# NBMC_SCHEMATIC_with_LBM313.net
KiCad netlist of a schematic drawn in EAGLE
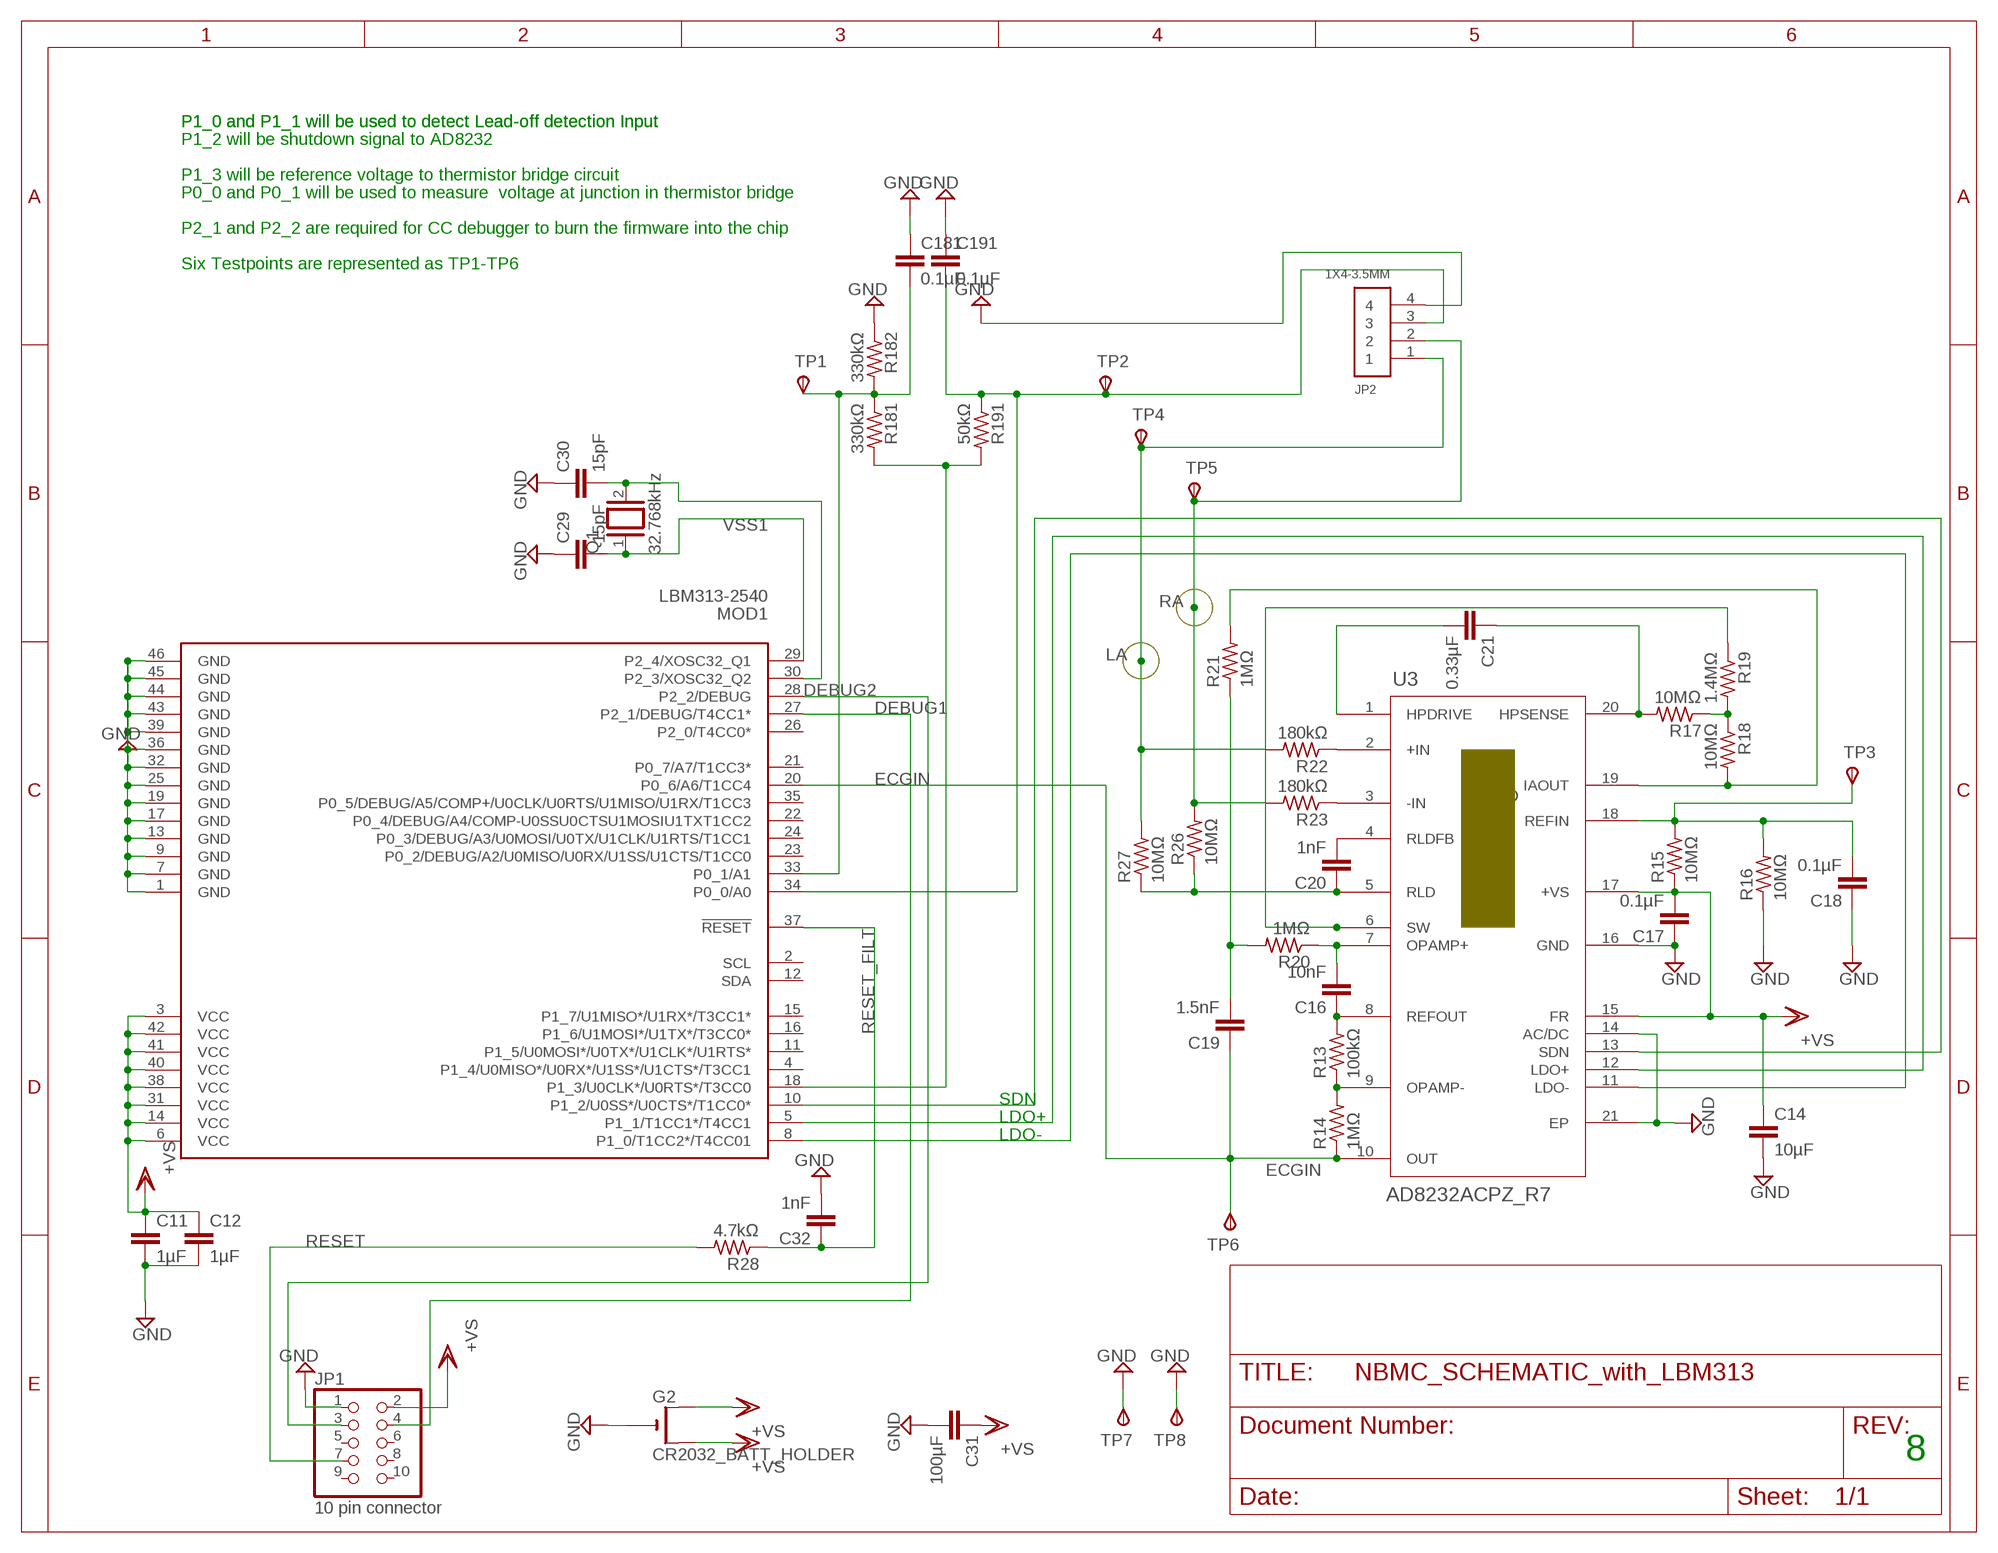
[diagram p0: schematic, sheet 1]

(export (version "E")
  (design (tool "Eeschema 10.0.6"))
  (components
    (comp (ref "C11")
      (value "1µF")
      (footprint "eagle-import:C0402")
      (libsource (lib "eagle-import") (part "C-EUC0402"))
    )
    (comp (ref "C12")
      (value "1µF")
      (footprint "eagle-import:C0402")
      (libsource (lib "eagle-import") (part "C-EUC0402"))
    )
    (comp (ref "C14")
      (value "10µF")
      (footprint "eagle-import:C0402")
      (libsource (lib "eagle-import") (part "C-EUC0402"))
    )
    (comp (ref "C16")
      (value "10nF")
      (footprint "eagle-import:C0402")
      (libsource (lib "eagle-import") (part "C-EUC0402"))
    )
    (comp (ref "C17")
      (value "0.1µF")
      (footprint "eagle-import:C0402")
      (libsource (lib "eagle-import") (part "C-EUC0402"))
    )
    (comp (ref "C18")
      (value "0.1µF")
      (footprint "eagle-import:C0402")
      (libsource (lib "eagle-import") (part "C-EUC0402"))
    )
    (comp (ref "C19")
      (value "1.5nF")
      (footprint "eagle-import:C0402")
      (libsource (lib "eagle-import") (part "C-EUC0402"))
    )
    (comp (ref "C20")
      (value "1nF")
      (footprint "eagle-import:C0402")
      (libsource (lib "eagle-import") (part "C-EUC0402"))
    )
    (comp (ref "C21")
      (value "0.33µF")
      (footprint "eagle-import:C0402")
      (libsource (lib "eagle-import") (part "C-EUC0402"))
    )
    (comp (ref "C29")
      (value "15pF")
      (footprint "eagle-import:C0402")
      (libsource (lib "eagle-import") (part "C-EUC0402"))
    )
    (comp (ref "C30")
      (value "15pF")
      (footprint "eagle-import:C0402")
      (libsource (lib "eagle-import") (part "C-EUC0402"))
    )
    (comp (ref "C31")
      (value "100µF")
      (footprint "eagle-import:C1210")
      (libsource (lib "eagle-import") (part "resistor_C-EUC1210"))
    )
    (comp (ref "C32")
      (value "1nF")
      (footprint "eagle-import:C0402")
      (libsource (lib "eagle-import") (part "C-EUC0402"))
    )
    (comp (ref "C181")
      (value "0.1µF")
      (footprint "eagle-import:C0402")
      (libsource (lib "eagle-import") (part "C-EUC0402"))
    )
    (comp (ref "C191")
      (value "0.1µF")
      (footprint "eagle-import:C0402")
      (libsource (lib "eagle-import") (part "C-EUC0402"))
    )
    (comp (ref "G2")
      (value "CR2032_BATT_HOLDER")
      (footprint "eagle-import:CR2032-SMD")
      (libsource (lib "eagle-import") (part "CR2032SMT"))
    )
    (comp (ref "JP1")
      (value "10 pin connector")
      (footprint "eagle-import:2X05")
      (libsource (lib "eagle-import") (part "PINHD-2X5"))
    )
    (comp (ref "JP2")
      (value "1X4-3.5MM")
      (footprint "eagle-import:1X04-3.5MM")
      (libsource (lib "eagle-import") (part "1X4-3.5MM"))
    )
    (comp (ref "MOD1")
      (value "LBM313-2540")
      (footprint "eagle-import:LBM313-2540")
      (libsource (lib "eagle-import") (part "LBM313-2540"))
    )
    (comp (ref "Q1")
      (value "32.768kHz")
      (footprint "eagle-import:Q")
      (libsource (lib "eagle-import") (part "XTAL"))
    )
    (comp (ref "R13")
      (value "100kΩ")
      (footprint "eagle-import:R0402")
      (libsource (lib "eagle-import") (part "R-US_R0402"))
    )
    (comp (ref "R14")
      (value "1MΩ")
      (footprint "eagle-import:R0402")
      (libsource (lib "eagle-import") (part "R-US_R0402"))
    )
    (comp (ref "R15")
      (value "10MΩ")
      (footprint "eagle-import:R0402")
      (libsource (lib "eagle-import") (part "R-US_R0402"))
    )
    (comp (ref "R16")
      (value "10MΩ")
      (footprint "eagle-import:R0402")
      (libsource (lib "eagle-import") (part "R-US_R0402"))
    )
    (comp (ref "R17")
      (value "10MΩ")
      (footprint "eagle-import:R0402")
      (libsource (lib "eagle-import") (part "R-US_R0402"))
    )
    (comp (ref "R18")
      (value "10MΩ")
      (footprint "eagle-import:R0402")
      (libsource (lib "eagle-import") (part "R-US_R0402"))
    )
    (comp (ref "R19")
      (value "1.4MΩ")
      (footprint "eagle-import:R0402")
      (libsource (lib "eagle-import") (part "R-US_R0402"))
    )
    (comp (ref "R20")
      (value "1MΩ")
      (footprint "eagle-import:R0402")
      (libsource (lib "eagle-import") (part "R-US_R0402"))
    )
    (comp (ref "R21")
      (value "1MΩ")
      (footprint "eagle-import:R0402")
      (libsource (lib "eagle-import") (part "R-US_R0402"))
    )
    (comp (ref "R22")
      (value "180kΩ")
      (footprint "eagle-import:R0402")
      (libsource (lib "eagle-import") (part "R-US_R0402"))
    )
    (comp (ref "R23")
      (value "180kΩ")
      (footprint "eagle-import:R0402")
      (libsource (lib "eagle-import") (part "R-US_R0402"))
    )
    (comp (ref "R26")
      (value "10MΩ")
      (footprint "eagle-import:R0402")
      (libsource (lib "eagle-import") (part "R-US_R0402"))
    )
    (comp (ref "R27")
      (value "10MΩ")
      (footprint "eagle-import:R0402")
      (libsource (lib "eagle-import") (part "R-US_R0402"))
    )
    (comp (ref "R28")
      (value "4.7kΩ")
      (footprint "eagle-import:R0402")
      (libsource (lib "eagle-import") (part "R-US_R0402"))
    )
    (comp (ref "R181")
      (value "330kΩ")
      (footprint "eagle-import:R0402")
      (libsource (lib "eagle-import") (part "R-US_R0402"))
    )
    (comp (ref "R182")
      (value "330kΩ")
      (footprint "eagle-import:R0402")
      (libsource (lib "eagle-import") (part "R-US_R0402"))
    )
    (comp (ref "R191")
      (value "50kΩ")
      (footprint "eagle-import:R0402")
      (libsource (lib "eagle-import") (part "R-US_R0402"))
    )
    (comp (ref "TP1")
      (value "TPSTP09R")
      (footprint "eagle-import:TP09R")
      (libsource (lib "eagle-import") (part "TPSTP09R"))
    )
    (comp (ref "TP2")
      (value "TPSTP09R")
      (footprint "eagle-import:TP09R")
      (libsource (lib "eagle-import") (part "TPSTP09R"))
    )
    (comp (ref "TP3")
      (value "TPSTP09R")
      (footprint "eagle-import:TP09R")
      (libsource (lib "eagle-import") (part "TPSTP09R"))
    )
    (comp (ref "TP4")
      (value "TPSTP09R")
      (footprint "eagle-import:TP09R")
      (libsource (lib "eagle-import") (part "TPSTP09R"))
    )
    (comp (ref "TP5")
      (value "TPSTP09R")
      (footprint "eagle-import:TP09R")
      (libsource (lib "eagle-import") (part "TPSTP09R"))
    )
    (comp (ref "TP6")
      (value "TPSTP09R")
      (footprint "eagle-import:TP09R")
      (libsource (lib "eagle-import") (part "TPSTP09R"))
    )
    (comp (ref "TP7")
      (value "TPSTP09R")
      (footprint "eagle-import:TP09R")
      (libsource (lib "eagle-import") (part "TPSTP09R"))
    )
    (comp (ref "TP8")
      (value "TPSTP09R")
      (footprint "eagle-import:TP09R")
      (libsource (lib "eagle-import") (part "TPSTP09R"))
    )
    (comp (ref "U3")
      (value "AD8232ACPZ_R7")
      (footprint "eagle-import:CP_20_10")
      (libsource (lib "eagle-import") (part "AD8232ACPZ_R7"))
    )
  )
  (nets
    (net (code "1") (name "+VS") (class "Default")
      (node (ref "C11") (pin "1") (pinfunction "1_1") (pintype "passive"))
      (node (ref "C12") (pin "1") (pinfunction "1_1") (pintype "passive"))
      (node (ref "C14") (pin "1") (pinfunction "1_1") (pintype "passive"))
      (node (ref "C17") (pin "2") (pinfunction "2_2") (pintype "passive"))
      (node (ref "C31") (pin "1") (pinfunction "1_1") (pintype "passive"))
      (node (ref "G2") (pin "1") (pinfunction "VS1_1") (pintype "passive"))
      (node (ref "G2") (pin "3") (pinfunction "VS2_3") (pintype "passive"))
      (node (ref "JP1") (pin "2") (pinfunction "2_2") (pintype "passive"))
      (node (ref "MOD1") (pin "14") (pinfunction "VCC_14") (pintype "bidirectional"))
      (node (ref "MOD1") (pin "3") (pinfunction "VCC_3") (pintype "bidirectional"))
      (node (ref "MOD1") (pin "31") (pinfunction "VCC_31") (pintype "bidirectional"))
      (node (ref "MOD1") (pin "38") (pinfunction "VCC_38") (pintype "bidirectional"))
      (node (ref "MOD1") (pin "40") (pinfunction "VCC_40") (pintype "bidirectional"))
      (node (ref "MOD1") (pin "41") (pinfunction "VCC_41") (pintype "bidirectional"))
      (node (ref "MOD1") (pin "42") (pinfunction "VCC_42") (pintype "bidirectional"))
      (node (ref "MOD1") (pin "6") (pinfunction "VCC_6") (pintype "bidirectional"))
      (node (ref "R15") (pin "1") (pinfunction "1_1") (pintype "passive"))
      (node (ref "U3") (pin "15") (pinfunction "FR_15") (pintype "passive"))
      (node (ref "U3") (pin "17") (pinfunction "+VS_17") (pintype "passive"))
    )
    (net (code "2") (name "/DEBUG1") (class "Default")
      (node (ref "JP1") (pin "4") (pinfunction "4_4") (pintype "passive"))
      (node (ref "MOD1") (pin "27") (pinfunction "P2_1/DEBUG/T4CC1*_27") (pintype "bidirectional"))
    )
    (net (code "3") (name "/DEBUG2") (class "Default")
      (node (ref "JP1") (pin "3") (pinfunction "3_3") (pintype "passive"))
      (node (ref "MOD1") (pin "28") (pinfunction "P2_2/DEBUG_28") (pintype "bidirectional"))
    )
    (net (code "4") (name "/ECGIN") (class "Default")
      (node (ref "C19") (pin "1") (pinfunction "1_1") (pintype "passive"))
      (node (ref "MOD1") (pin "20") (pinfunction "P0_6/A6/T1CC4_20") (pintype "bidirectional"))
      (node (ref "R14") (pin "1") (pinfunction "1_1") (pintype "passive"))
      (node (ref "TP6") (pin "TP") (pinfunction "PP_TP") (pintype "input"))
      (node (ref "U3") (pin "10") (pinfunction "OUT_10") (pintype "passive"))
    )
    (net (code "5") (name "/LA") (class "Default")
      (node (ref "JP2") (pin "1") (pinfunction "1_1") (pintype "bidirectional"))
      (node (ref "R22") (pin "2") (pinfunction "2_2") (pintype "passive"))
      (node (ref "R27") (pin "2") (pinfunction "2_2") (pintype "passive"))
      (node (ref "TP4") (pin "TP") (pinfunction "PP_TP") (pintype "input"))
    )
    (net (code "6") (name "/RA") (class "Default")
      (node (ref "JP2") (pin "2") (pinfunction "2_2") (pintype "bidirectional"))
      (node (ref "R23") (pin "2") (pinfunction "2_2") (pintype "passive"))
      (node (ref "R26") (pin "2") (pinfunction "2_2") (pintype "passive"))
      (node (ref "TP5") (pin "TP") (pinfunction "PP_TP") (pintype "input"))
    )
    (net (code "7") (name "/RESET") (class "Default")
      (node (ref "JP1") (pin "7") (pinfunction "7_7") (pintype "passive"))
      (node (ref "R28") (pin "2") (pinfunction "2_2") (pintype "passive"))
    )
    (net (code "8") (name "/RESET_FILT") (class "Default")
      (node (ref "C32") (pin "1") (pinfunction "1_1") (pintype "passive"))
      (node (ref "MOD1") (pin "37") (pinfunction "~{RESET}_37") (pintype "bidirectional"))
      (node (ref "R28") (pin "1") (pinfunction "1_1") (pintype "passive"))
    )
    (net (code "9") (name "/VSS1") (class "Default")
      (node (ref "C29") (pin "2") (pinfunction "2_2") (pintype "passive"))
      (node (ref "MOD1") (pin "29") (pinfunction "P2_4/XOSC32_Q1_29") (pintype "bidirectional"))
      (node (ref "Q1") (pin "1") (pinfunction "1_1") (pintype "passive"))
    )
    (net (code "10") (name "GND") (class "Default")
      (node (ref "C11") (pin "2") (pinfunction "2_2") (pintype "passive"))
      (node (ref "C12") (pin "2") (pinfunction "2_2") (pintype "passive"))
      (node (ref "C14") (pin "2") (pinfunction "2_2") (pintype "passive"))
      (node (ref "C17") (pin "1") (pinfunction "1_1") (pintype "passive"))
      (node (ref "C18") (pin "1") (pinfunction "1_1") (pintype "passive"))
      (node (ref "C181") (pin "1") (pinfunction "1_1") (pintype "passive"))
      (node (ref "C191") (pin "1") (pinfunction "1_1") (pintype "passive"))
      (node (ref "C29") (pin "1") (pinfunction "1_1") (pintype "passive"))
      (node (ref "C30") (pin "1") (pinfunction "1_1") (pintype "passive"))
      (node (ref "C31") (pin "2") (pinfunction "2_2") (pintype "passive"))
      (node (ref "C32") (pin "2") (pinfunction "2_2") (pintype "passive"))
      (node (ref "G2") (pin "2") (pinfunction "GND_2") (pintype "passive"))
      (node (ref "JP1") (pin "1") (pinfunction "1_1") (pintype "passive"))
      (node (ref "JP2") (pin "4") (pinfunction "4_4") (pintype "bidirectional"))
      (node (ref "MOD1") (pin "1") (pinfunction "GND_1") (pintype "bidirectional"))
      (node (ref "MOD1") (pin "13") (pinfunction "GND_13") (pintype "bidirectional"))
      (node (ref "MOD1") (pin "17") (pinfunction "GND_17") (pintype "bidirectional"))
      (node (ref "MOD1") (pin "19") (pinfunction "GND_19") (pintype "bidirectional"))
      (node (ref "MOD1") (pin "25") (pinfunction "GND_25") (pintype "bidirectional"))
      (node (ref "MOD1") (pin "32") (pinfunction "GND_32") (pintype "bidirectional"))
      (node (ref "MOD1") (pin "36") (pinfunction "GND_36") (pintype "bidirectional"))
      (node (ref "MOD1") (pin "39") (pinfunction "GND_39") (pintype "bidirectional"))
      (node (ref "MOD1") (pin "43") (pinfunction "GND_43") (pintype "bidirectional"))
      (node (ref "MOD1") (pin "44") (pinfunction "GND_44") (pintype "bidirectional"))
      (node (ref "MOD1") (pin "45") (pinfunction "GND_45") (pintype "bidirectional"))
      (node (ref "MOD1") (pin "46") (pinfunction "GND_46") (pintype "bidirectional"))
      (node (ref "MOD1") (pin "7") (pinfunction "GND_7") (pintype "bidirectional"))
      (node (ref "MOD1") (pin "9") (pinfunction "GND_9") (pintype "bidirectional"))
      (node (ref "R16") (pin "1") (pinfunction "1_1") (pintype "passive"))
      (node (ref "R182") (pin "1") (pinfunction "1_1") (pintype "passive"))
      (node (ref "TP7") (pin "TP") (pinfunction "PP_TP") (pintype "input"))
      (node (ref "TP8") (pin "TP") (pinfunction "PP_TP") (pintype "input"))
      (node (ref "U3") (pin "14") (pinfunction "AC/DC_14") (pintype "passive"))
      (node (ref "U3") (pin "16") (pinfunction "GND_16") (pintype "passive"))
      (node (ref "U3") (pin "21") (pinfunction "EP_21") (pintype "passive"))
    )
    (net (code "11") (name "Net-(C19-Pad2)") (class "Default")
      (node (ref "C19") (pin "2") (pinfunction "2_2") (pintype "passive"))
      (node (ref "R20") (pin "2") (pinfunction "2_2") (pintype "passive"))
      (node (ref "R21") (pin "1") (pinfunction "1_1") (pintype "passive"))
    )
    (net (code "12") (name "Net-(MOD1-P0_0{slash}A0)") (class "Default")
      (node (ref "C191") (pin "2") (pinfunction "2_2") (pintype "passive"))
      (node (ref "JP2") (pin "3") (pinfunction "3_3") (pintype "bidirectional"))
      (node (ref "MOD1") (pin "34") (pinfunction "P0_0/A0_34") (pintype "bidirectional"))
      (node (ref "R191") (pin "1") (pinfunction "1_1") (pintype "passive"))
      (node (ref "TP2") (pin "TP") (pinfunction "PP_TP") (pintype "input"))
    )
    (net (code "13") (name "Net-(MOD1-P0_1{slash}A1)") (class "Default")
      (node (ref "C181") (pin "2") (pinfunction "2_2") (pintype "passive"))
      (node (ref "MOD1") (pin "33") (pinfunction "P0_1/A1_33") (pintype "bidirectional"))
      (node (ref "R181") (pin "1") (pinfunction "1_1") (pintype "passive"))
      (node (ref "R182") (pin "2") (pinfunction "2_2") (pintype "passive"))
      (node (ref "TP1") (pin "TP") (pinfunction "PP_TP") (pintype "input"))
    )
    (net (code "14") (name "Net-(MOD1-P1_0{slash}T1CC2*{slash}T4CC01)") (class "Default")
      (node (ref "MOD1") (pin "8") (pinfunction "P1_0/T1CC2*/T4CC01_8") (pintype "bidirectional"))
      (node (ref "U3") (pin "11") (pinfunction "LDO-_11") (pintype "passive"))
    )
    (net (code "15") (name "Net-(MOD1-P1_1{slash}T1CC1*{slash}T4CC1)") (class "Default")
      (node (ref "MOD1") (pin "5") (pinfunction "P1_1/T1CC1*/T4CC1_5") (pintype "bidirectional"))
      (node (ref "U3") (pin "12") (pinfunction "LDO+_12") (pintype "passive"))
    )
    (net (code "16") (name "Net-(MOD1-P1_2{slash}U0SS*{slash}U0CTS*{slash}T1CC0*)") (class "Default")
      (node (ref "MOD1") (pin "10") (pinfunction "P1_2/U0SS*/U0CTS*/T1CC0*_10") (pintype "bidirectional"))
      (node (ref "U3") (pin "13") (pinfunction "SDN_13") (pintype "passive"))
    )
    (net (code "17") (name "Net-(MOD1-P1_3{slash}U0CLK*{slash}U0RTS*{slash}T3CC0)") (class "Default")
      (node (ref "MOD1") (pin "18") (pinfunction "P1_3/U0CLK*/U0RTS*/T3CC0_18") (pintype "bidirectional"))
      (node (ref "R181") (pin "2") (pinfunction "2_2") (pintype "passive"))
      (node (ref "R191") (pin "2") (pinfunction "2_2") (pintype "passive"))
    )
    (net (code "18") (name "Net-(MOD1-P2_3{slash}XOSC32_Q2)") (class "Default")
      (node (ref "C30") (pin "2") (pinfunction "2_2") (pintype "passive"))
      (node (ref "MOD1") (pin "30") (pinfunction "P2_3/XOSC32_Q2_30") (pintype "bidirectional"))
      (node (ref "Q1") (pin "2") (pinfunction "2_2") (pintype "passive"))
    )
    (net (code "19") (name "Net-(R17-Pad1)") (class "Default")
      (node (ref "R17") (pin "1") (pinfunction "1_1") (pintype "passive"))
      (node (ref "R18") (pin "1") (pinfunction "1_1") (pintype "passive"))
      (node (ref "R19") (pin "2") (pinfunction "2_2") (pintype "passive"))
    )
    (net (code "20") (name "Net-(TP3-PP)") (class "Default")
      (node (ref "C18") (pin "2") (pinfunction "2_2") (pintype "passive"))
      (node (ref "R15") (pin "2") (pinfunction "2_2") (pintype "passive"))
      (node (ref "R16") (pin "2") (pinfunction "2_2") (pintype "passive"))
      (node (ref "TP3") (pin "TP") (pinfunction "PP_TP") (pintype "input"))
      (node (ref "U3") (pin "18") (pinfunction "REFIN_18") (pintype "passive"))
    )
    (net (code "21") (name "Net-(U3-+IN)") (class "Default")
      (node (ref "R22") (pin "1") (pinfunction "1_1") (pintype "passive"))
      (node (ref "U3") (pin "2") (pinfunction "+IN_2") (pintype "passive"))
    )
    (net (code "22") (name "Net-(U3--IN)") (class "Default")
      (node (ref "R23") (pin "1") (pinfunction "1_1") (pintype "passive"))
      (node (ref "U3") (pin "3") (pinfunction "-IN_3") (pintype "passive"))
    )
    (net (code "23") (name "Net-(U3-HPDRIVE)") (class "Default")
      (node (ref "C21") (pin "2") (pinfunction "2_2") (pintype "passive"))
      (node (ref "U3") (pin "1") (pinfunction "HPDRIVE_1") (pintype "passive"))
    )
    (net (code "24") (name "Net-(U3-HPSENSE)") (class "Default")
      (node (ref "C21") (pin "1") (pinfunction "1_1") (pintype "passive"))
      (node (ref "R17") (pin "2") (pinfunction "2_2") (pintype "passive"))
      (node (ref "U3") (pin "20") (pinfunction "HPSENSE_20") (pintype "passive"))
    )
    (net (code "25") (name "Net-(U3-IAOUT)") (class "Default")
      (node (ref "R18") (pin "2") (pinfunction "2_2") (pintype "passive"))
      (node (ref "R21") (pin "2") (pinfunction "2_2") (pintype "passive"))
      (node (ref "U3") (pin "19") (pinfunction "IAOUT_19") (pintype "passive"))
    )
    (net (code "26") (name "Net-(U3-OPAMP+)") (class "Default")
      (node (ref "C16") (pin "2") (pinfunction "2_2") (pintype "passive"))
      (node (ref "R20") (pin "1") (pinfunction "1_1") (pintype "passive"))
      (node (ref "U3") (pin "7") (pinfunction "OPAMP+_7") (pintype "passive"))
    )
    (net (code "27") (name "Net-(U3-OPAMP-)") (class "Default")
      (node (ref "R13") (pin "1") (pinfunction "1_1") (pintype "passive"))
      (node (ref "R14") (pin "2") (pinfunction "2_2") (pintype "passive"))
      (node (ref "U3") (pin "9") (pinfunction "OPAMP-_9") (pintype "passive"))
    )
    (net (code "28") (name "Net-(U3-REFOUT)") (class "Default")
      (node (ref "C16") (pin "1") (pinfunction "1_1") (pintype "passive"))
      (node (ref "R13") (pin "2") (pinfunction "2_2") (pintype "passive"))
      (node (ref "U3") (pin "8") (pinfunction "REFOUT_8") (pintype "passive"))
    )
    (net (code "29") (name "Net-(U3-RLD)") (class "Default")
      (node (ref "C20") (pin "1") (pinfunction "1_1") (pintype "passive"))
      (node (ref "R26") (pin "1") (pinfunction "1_1") (pintype "passive"))
      (node (ref "R27") (pin "1") (pinfunction "1_1") (pintype "passive"))
      (node (ref "U3") (pin "5") (pinfunction "RLD_5") (pintype "passive"))
    )
    (net (code "30") (name "Net-(U3-RLDFB)") (class "Default")
      (node (ref "C20") (pin "2") (pinfunction "2_2") (pintype "passive"))
      (node (ref "U3") (pin "4") (pinfunction "RLDFB_4") (pintype "passive"))
    )
    (net (code "31") (name "Net-(U3-SW)") (class "Default")
      (node (ref "R19") (pin "1") (pinfunction "1_1") (pintype "passive"))
      (node (ref "U3") (pin "6") (pinfunction "SW_6") (pintype "passive"))
    )
    (net (code "32") (name "unconnected-(JP1-Pad5)") (class "Default")
      (node (ref "JP1") (pin "5") (pinfunction "5_5") (pintype "passive"))
    )
    (net (code "33") (name "unconnected-(JP1-Pad6)") (class "Default")
      (node (ref "JP1") (pin "6") (pinfunction "6_6") (pintype "passive"))
    )
    (net (code "34") (name "unconnected-(JP1-Pad8)") (class "Default")
      (node (ref "JP1") (pin "8") (pinfunction "8_8") (pintype "passive"))
    )
    (net (code "35") (name "unconnected-(JP1-Pad9)") (class "Default")
      (node (ref "JP1") (pin "9") (pinfunction "9_9") (pintype "passive"))
    )
    (net (code "36") (name "unconnected-(JP1-Pad10)") (class "Default")
      (node (ref "JP1") (pin "10") (pinfunction "10_10") (pintype "passive"))
    )
    (net (code "37") (name "unconnected-(MOD1-P0_2{slash}DEBUG{slash}A2{slash}U0MISO{slash}U0RX{slash}U1SS{slash}U1CTS{slash}T1CC0-Pad23)") (class "Default")
      (node (ref "MOD1") (pin "23") (pinfunction "P0_2/DEBUG/A2/U0MISO/U0RX/U1SS/U1CTS/T1CC0_23") (pintype "bidirectional"))
    )
    (net (code "38") (name "unconnected-(MOD1-P0_3{slash}DEBUG{slash}A3{slash}U0MOSI{slash}U0TX{slash}U1CLK{slash}U1RTS{slash}T1CC1-Pad24)") (class "Default")
      (node (ref "MOD1") (pin "24") (pinfunction "P0_3/DEBUG/A3/U0MOSI/U0TX/U1CLK/U1RTS/T1CC1_24") (pintype "bidirectional"))
    )
    (net (code "39") (name "unconnected-(MOD1-P0_4{slash}DEBUG{slash}A4{slash}COMP-U0SSU0CTSU1MOSIU1TXT1CC2-Pad22)") (class "Default")
      (node (ref "MOD1") (pin "22") (pinfunction "P0_4/DEBUG/A4/COMP-U0SSU0CTSU1MOSIU1TXT1CC2_22") (pintype "bidirectional"))
    )
    (net (code "40") (name "unconnected-(MOD1-P0_5{slash}DEBUG{slash}A5{slash}COMP+{slash}U0CLK{slash}U0RTS{slash}U1MISO{slash}U1RX{slash}T1CC3-Pad35)") (class "Default")
      (node (ref "MOD1") (pin "35") (pinfunction "P0_5/DEBUG/A5/COMP+/U0CLK/U0RTS/U1MISO/U1RX/T1CC3_35") (pintype "bidirectional"))
    )
    (net (code "41") (name "unconnected-(MOD1-P0_7{slash}A7{slash}T1CC3*-Pad21)") (class "Default")
      (node (ref "MOD1") (pin "21") (pinfunction "P0_7/A7/T1CC3*_21") (pintype "bidirectional"))
    )
    (net (code "42") (name "unconnected-(MOD1-P1_4{slash}U0MISO*{slash}U0RX*{slash}U1SS*{slash}U1CTS*{slash}T3CC1-Pad4)") (class "Default")
      (node (ref "MOD1") (pin "4") (pinfunction "P1_4/U0MISO*/U0RX*/U1SS*/U1CTS*/T3CC1_4") (pintype "bidirectional"))
    )
    (net (code "43") (name "unconnected-(MOD1-P1_5{slash}U0MOSI*{slash}U0TX*{slash}U1CLK*{slash}U1RTS*-Pad11)") (class "Default")
      (node (ref "MOD1") (pin "11") (pinfunction "P1_5/U0MOSI*/U0TX*/U1CLK*/U1RTS*_11") (pintype "bidirectional"))
    )
    (net (code "44") (name "unconnected-(MOD1-P1_6{slash}U1MOSI*{slash}U1TX*{slash}T3CC0*-Pad16)") (class "Default")
      (node (ref "MOD1") (pin "16") (pinfunction "P1_6/U1MOSI*/U1TX*/T3CC0*_16") (pintype "bidirectional"))
    )
    (net (code "45") (name "unconnected-(MOD1-P1_7{slash}U1MISO*{slash}U1RX*{slash}T3CC1*-Pad15)") (class "Default")
      (node (ref "MOD1") (pin "15") (pinfunction "P1_7/U1MISO*/U1RX*/T3CC1*_15") (pintype "bidirectional"))
    )
    (net (code "46") (name "unconnected-(MOD1-P2_0{slash}T4CC0*-Pad26)") (class "Default")
      (node (ref "MOD1") (pin "26") (pinfunction "P2_0/T4CC0*_26") (pintype "bidirectional"))
    )
    (net (code "47") (name "unconnected-(MOD1-SCL-Pad2)") (class "Default")
      (node (ref "MOD1") (pin "2") (pinfunction "SCL_2") (pintype "bidirectional"))
    )
    (net (code "48") (name "unconnected-(MOD1-SDA-Pad12)") (class "Default")
      (node (ref "MOD1") (pin "12") (pinfunction "SDA_12") (pintype "bidirectional"))
    )
  )
)
